# FT232.net
KiCad netlist of a schematic drawn in EAGLE
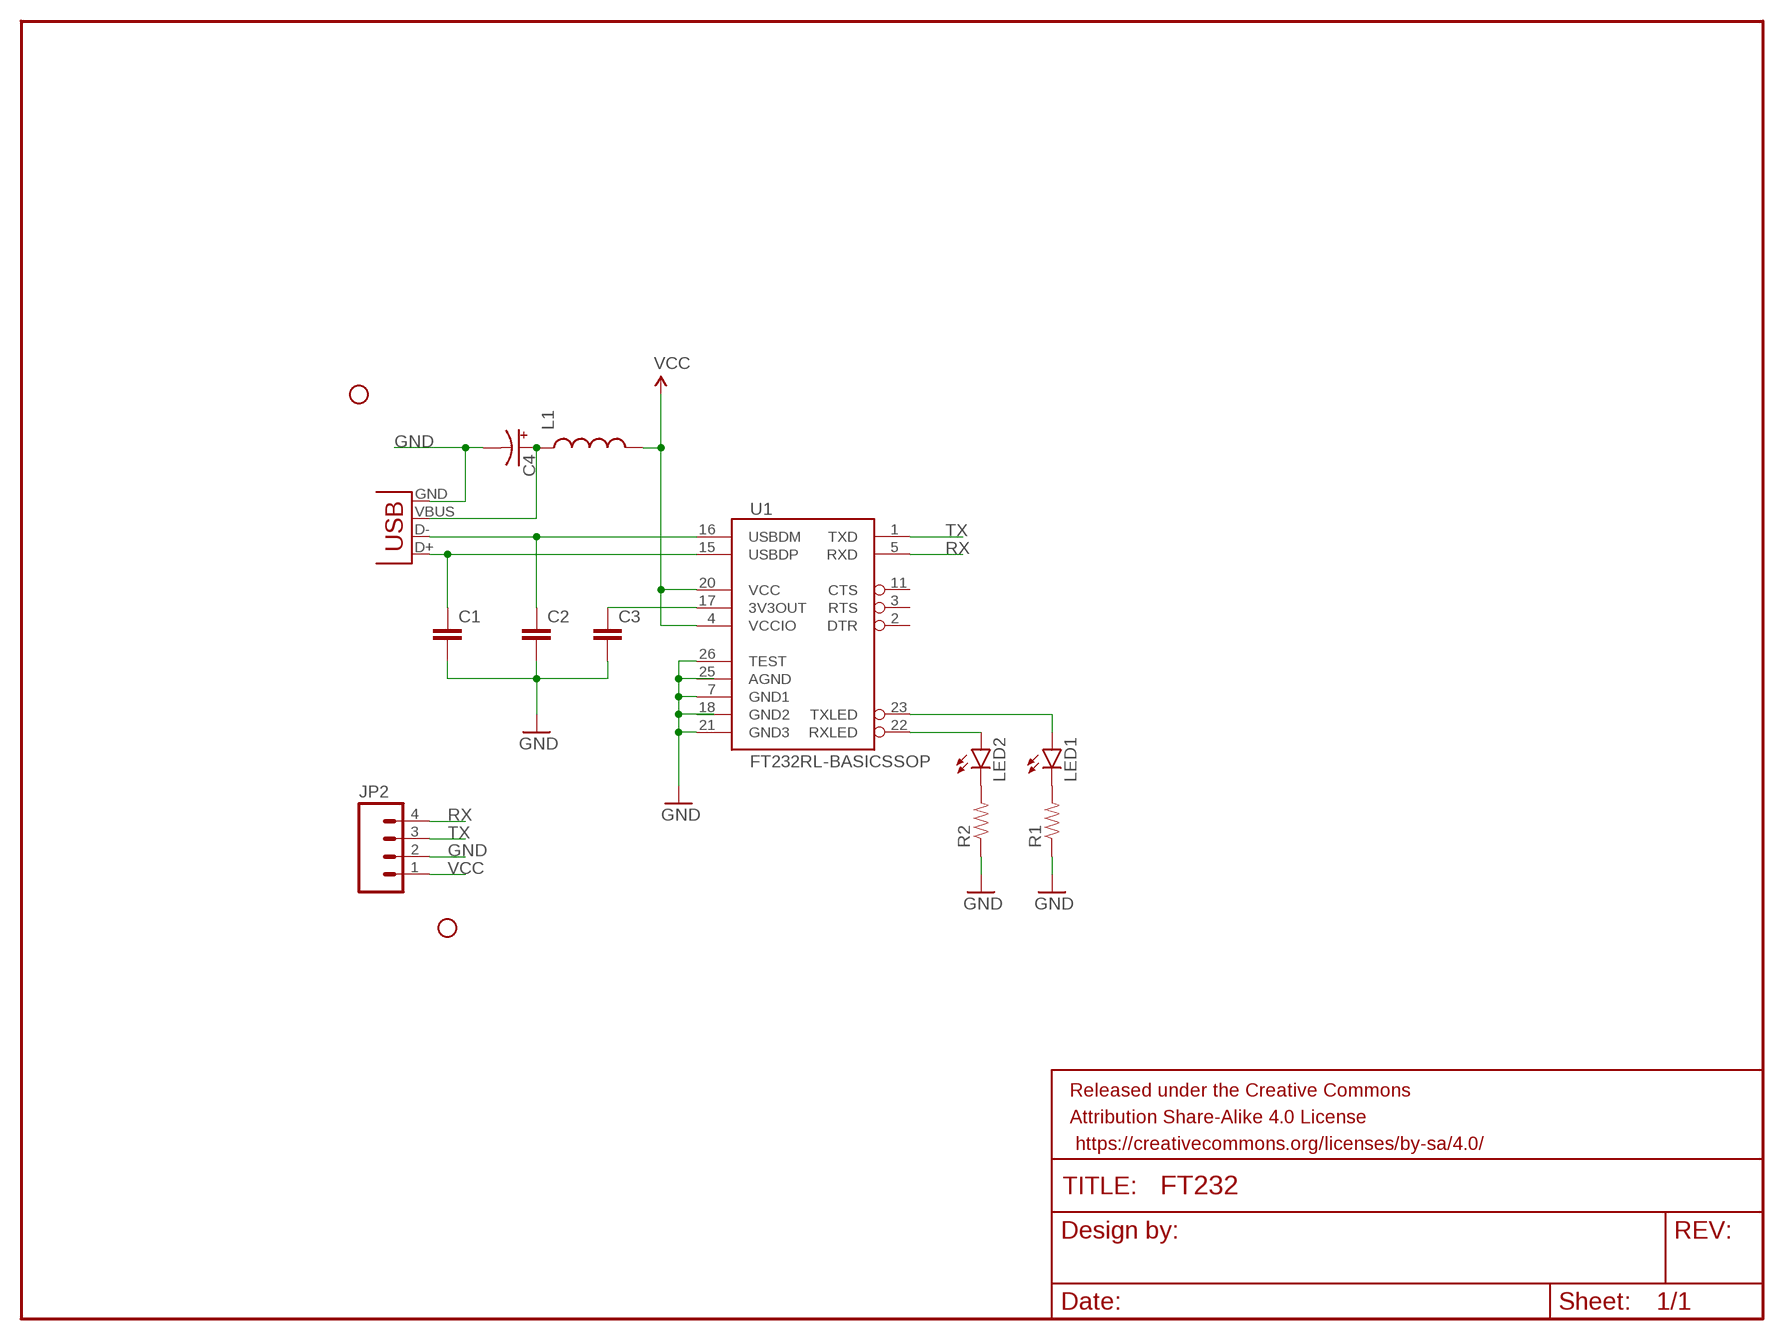
[diagram p0: schematic, sheet 1]

(export (version "E")
  (design (tool "Eeschema 10.0.6"))
  (components
    (comp (ref "C1")
      (value "CAP0603-CAP")
      (footprint "eagle-import:0603-CAP")
      (libsource (lib "eagle-import") (part "CAP0603-CAP"))
    )
    (comp (ref "C2")
      (value "CAP0603-CAP")
      (footprint "eagle-import:0603-CAP")
      (libsource (lib "eagle-import") (part "CAP0603-CAP"))
    )
    (comp (ref "C3")
      (value "CAP0603-CAP")
      (footprint "eagle-import:0603-CAP")
      (libsource (lib "eagle-import") (part "CAP0603-CAP"))
    )
    (comp (ref "C4")
      (value "CAP_POL1206")
      (footprint "eagle-import:EIA3216")
      (libsource (lib "eagle-import") (part "CAP_POL1206"))
    )
    (comp (ref "FRAME1")
      (value "FRAME-LETTER")
      (footprint "eagle-import:CREATIVE_COMMONS")
      (libsource (lib "eagle-import") (part "FRAME-LETTER"))
    )
    (comp (ref "JP1")
      (value "USB-B")
      (footprint "eagle-import:USB-B-PTH")
      (libsource (lib "eagle-import") (part "USBPTH"))
    )
    (comp (ref "JP2")
      (value "M04PTH")
      (footprint "eagle-import:1X04")
      (libsource (lib "eagle-import") (part "M04PTH"))
    )
    (comp (ref "L1")
      (value "INDUCTOR0603")
      (footprint "eagle-import:0603")
      (libsource (lib "eagle-import") (part "INDUCTOR0603"))
    )
    (comp (ref "LED1")
      (value "LED5MM")
      (footprint "eagle-import:LED5MM")
      (libsource (lib "eagle-import") (part "LED5MM"))
    )
    (comp (ref "LED2")
      (value "LED5MM")
      (footprint "eagle-import:LED5MM")
      (libsource (lib "eagle-import") (part "LED5MM"))
    )
    (comp (ref "R1")
      (value "RESISTORPTH-1/4W")
      (footprint "eagle-import:AXIAL-0.4")
      (libsource (lib "eagle-import") (part "RESISTORPTH-1/4W"))
    )
    (comp (ref "R2")
      (value "RESISTORPTH-1/4W")
      (footprint "eagle-import:AXIAL-0.4")
      (libsource (lib "eagle-import") (part "RESISTORPTH-1/4W"))
    )
    (comp (ref "STANDOFF1")
      (value "STAND-OFF")
      (footprint "eagle-import:STAND-OFF")
      (libsource (lib "eagle-import") (part "STAND-OFF"))
    )
    (comp (ref "STANDOFF3")
      (value "STAND-OFF")
      (footprint "eagle-import:STAND-OFF")
      (libsource (lib "eagle-import") (part "STAND-OFF"))
    )
    (comp (ref "U1")
      (value "FT232RL-BASICSSOP")
      (footprint "eagle-import:SSOP28DB")
      (libsource (lib "eagle-import") (part "FT232RL-BASICSSOP"))
    )
  )
  (nets
    (net (code "1") (name "/AGND") (class "Default")
      (node (ref "U1") (pin "25") (pinfunction "AGND_25") (pintype "power_in"))
    )
    (net (code "2") (name "/GND2") (class "Default")
      (node (ref "U1") (pin "18") (pinfunction "GND2_18") (pintype "power_in"))
    )
    (net (code "3") (name "/RX") (class "Default")
      (node (ref "JP2") (pin "4") (pinfunction "4_4") (pintype "passive"))
      (node (ref "U1") (pin "5") (pinfunction "RXD_5") (pintype "input"))
    )
    (net (code "4") (name "/TX") (class "Default")
      (node (ref "JP2") (pin "3") (pinfunction "3_3") (pintype "passive"))
      (node (ref "U1") (pin "1") (pinfunction "TXD_1") (pintype "output"))
    )
    (net (code "5") (name "GND") (class "Default")
      (node (ref "C1") (pin "2") (pinfunction "2_2") (pintype "passive"))
      (node (ref "C2") (pin "2") (pinfunction "2_2") (pintype "passive"))
      (node (ref "C3") (pin "2") (pinfunction "2_2") (pintype "passive"))
      (node (ref "C4") (pin "C") (pinfunction "-_C") (pintype "passive"))
      (node (ref "JP1") (pin "GND") (pinfunction "GND_GND") (pintype "bidirectional"))
      (node (ref "JP2") (pin "2") (pinfunction "2_2") (pintype "passive"))
      (node (ref "R1") (pin "P$1") (pinfunction "1_P$1") (pintype "passive"))
      (node (ref "R2") (pin "P$1") (pinfunction "1_P$1") (pintype "passive"))
      (node (ref "U1") (pin "21") (pinfunction "GND3_21") (pintype "power_in"))
      (node (ref "U1") (pin "26") (pinfunction "TEST_26") (pintype "input"))
      (node (ref "U1") (pin "7") (pinfunction "GND1_7") (pintype "power_in"))
    )
    (net (code "6") (name "Net-(C4-+)") (class "Default")
      (node (ref "C4") (pin "A") (pinfunction "+_A") (pintype "passive"))
      (node (ref "JP1") (pin "VBUS") (pinfunction "VBUS_VBUS") (pintype "bidirectional"))
      (node (ref "L1") (pin "1") (pinfunction "1_1") (pintype "passive"))
    )
    (net (code "7") (name "Net-(LED1-C)") (class "Default")
      (node (ref "LED1") (pin "K") (pinfunction "C_K") (pintype "passive"))
      (node (ref "R1") (pin "P$2") (pinfunction "2_P$2") (pintype "passive"))
    )
    (net (code "8") (name "Net-(LED2-C)") (class "Default")
      (node (ref "LED2") (pin "K") (pinfunction "C_K") (pintype "passive"))
      (node (ref "R2") (pin "P$2") (pinfunction "2_P$2") (pintype "passive"))
    )
    (net (code "9") (name "Net-(U1-3V3OUT)") (class "Default")
      (node (ref "C3") (pin "1") (pinfunction "1_1") (pintype "passive"))
      (node (ref "U1") (pin "17") (pinfunction "3V3OUT_17") (pintype "output"))
    )
    (net (code "10") (name "Net-(U1-RXLED)") (class "Default")
      (node (ref "LED2") (pin "A") (pinfunction "A_A") (pintype "passive"))
      (node (ref "U1") (pin "22") (pinfunction "RXLED_22") (pintype "bidirectional"))
    )
    (net (code "11") (name "Net-(U1-TXLED)") (class "Default")
      (node (ref "LED1") (pin "A") (pinfunction "A_A") (pintype "passive"))
      (node (ref "U1") (pin "23") (pinfunction "TXLED_23") (pintype "bidirectional"))
    )
    (net (code "12") (name "Net-(U1-USBDM)") (class "Default")
      (node (ref "C2") (pin "1") (pinfunction "1_1") (pintype "passive"))
      (node (ref "JP1") (pin "D-") (pinfunction "D-_D-") (pintype "bidirectional"))
      (node (ref "U1") (pin "16") (pinfunction "USBDM_16") (pintype "bidirectional"))
    )
    (net (code "13") (name "Net-(U1-USBDP)") (class "Default")
      (node (ref "C1") (pin "1") (pinfunction "1_1") (pintype "passive"))
      (node (ref "JP1") (pin "D+") (pinfunction "D+_D+") (pintype "bidirectional"))
      (node (ref "U1") (pin "15") (pinfunction "USBDP_15") (pintype "bidirectional"))
    )
    (net (code "14") (name "VCC") (class "Default")
      (node (ref "JP2") (pin "1") (pinfunction "1_1") (pintype "passive"))
      (node (ref "L1") (pin "2") (pinfunction "2_2") (pintype "passive"))
      (node (ref "U1") (pin "20") (pinfunction "VCC_20") (pintype "power_in"))
      (node (ref "U1") (pin "4") (pinfunction "VCCIO_4") (pintype "power_in"))
    )
    (net (code "15") (name "unconnected-(U1-CTS-Pad11)") (class "Default")
      (node (ref "U1") (pin "11") (pinfunction "CTS_11") (pintype "bidirectional"))
    )
    (net (code "16") (name "unconnected-(U1-DTR-Pad2)") (class "Default")
      (node (ref "U1") (pin "2") (pinfunction "DTR_2") (pintype "bidirectional"))
    )
    (net (code "17") (name "unconnected-(U1-RTS-Pad3)") (class "Default")
      (node (ref "U1") (pin "3") (pinfunction "RTS_3") (pintype "bidirectional"))
    )
  )
)
